# HV_Measurements.net
KiCad netlist of a schematic drawn in Altium Designer
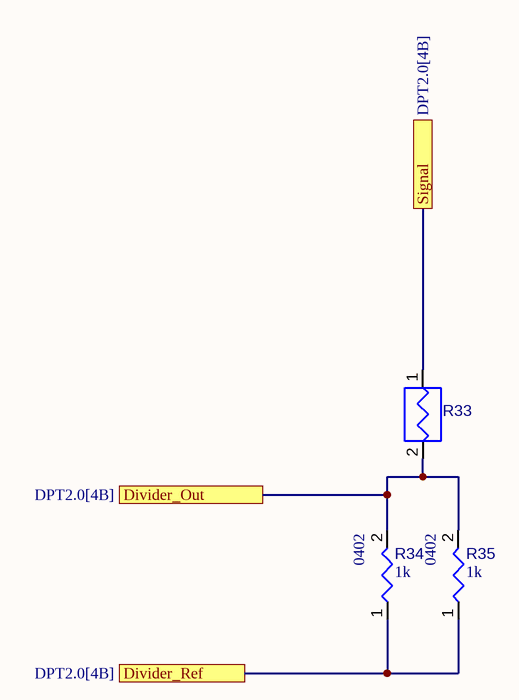
[diagram p0: HV_Measurements.SchDoc]

(export (version "E")
  (design (tool "Eeschema 10.0.6"))
  (components
    (comp (ref "R33")
      (value "RES-2512-SIDE")
      (footprint "RES_2512_SIDE")
      (description "SMD Resistor - 2512 (6432) On It's Side")
      (libsource (lib "2256-GaN Power") (part "RES-SIDE-2"))
    )
    (comp (ref "R34")
      (value "1k")
      (footprint "RES_0402_HIGH")
      (description "SMD Resistor - 0402 (1005 Metric)")
      (fields (field (name "Comment") "RES-0402"))
      (libsource (lib "2256-GaN Power") (part "RES-2"))
    )
    (comp (ref "R35")
      (value "1k")
      (footprint "RES_0402_HIGH")
      (description "SMD Resistor - 0402 (1005 Metric)")
      (fields (field (name "Comment") "RES-0402"))
      (libsource (lib "2256-GaN Power") (part "RES-2"))
    )
  )
  (nets
    (net (code "1") (name "/Divider_Out") (class "Default")
      (node (ref "R33") (pin "2") (pinfunction "2_2") (pintype "passive"))
      (node (ref "R34") (pin "2") (pinfunction "2_2") (pintype "passive"))
      (node (ref "R35") (pin "2") (pinfunction "2_2") (pintype "passive"))
    )
    (net (code "2") (name "/Divider_Ref") (class "Default")
      (node (ref "R34") (pin "1") (pinfunction "1_1") (pintype "passive"))
      (node (ref "R35") (pin "1") (pinfunction "1_1") (pintype "passive"))
    )
    (net (code "3") (name "/Signal") (class "Default")
      (node (ref "R33") (pin "1") (pinfunction "1_1") (pintype "passive"))
    )
  )
)
